# CarteAction_PontLevis2026.net
KiCad netlist of a schematic drawn in Altium Designer
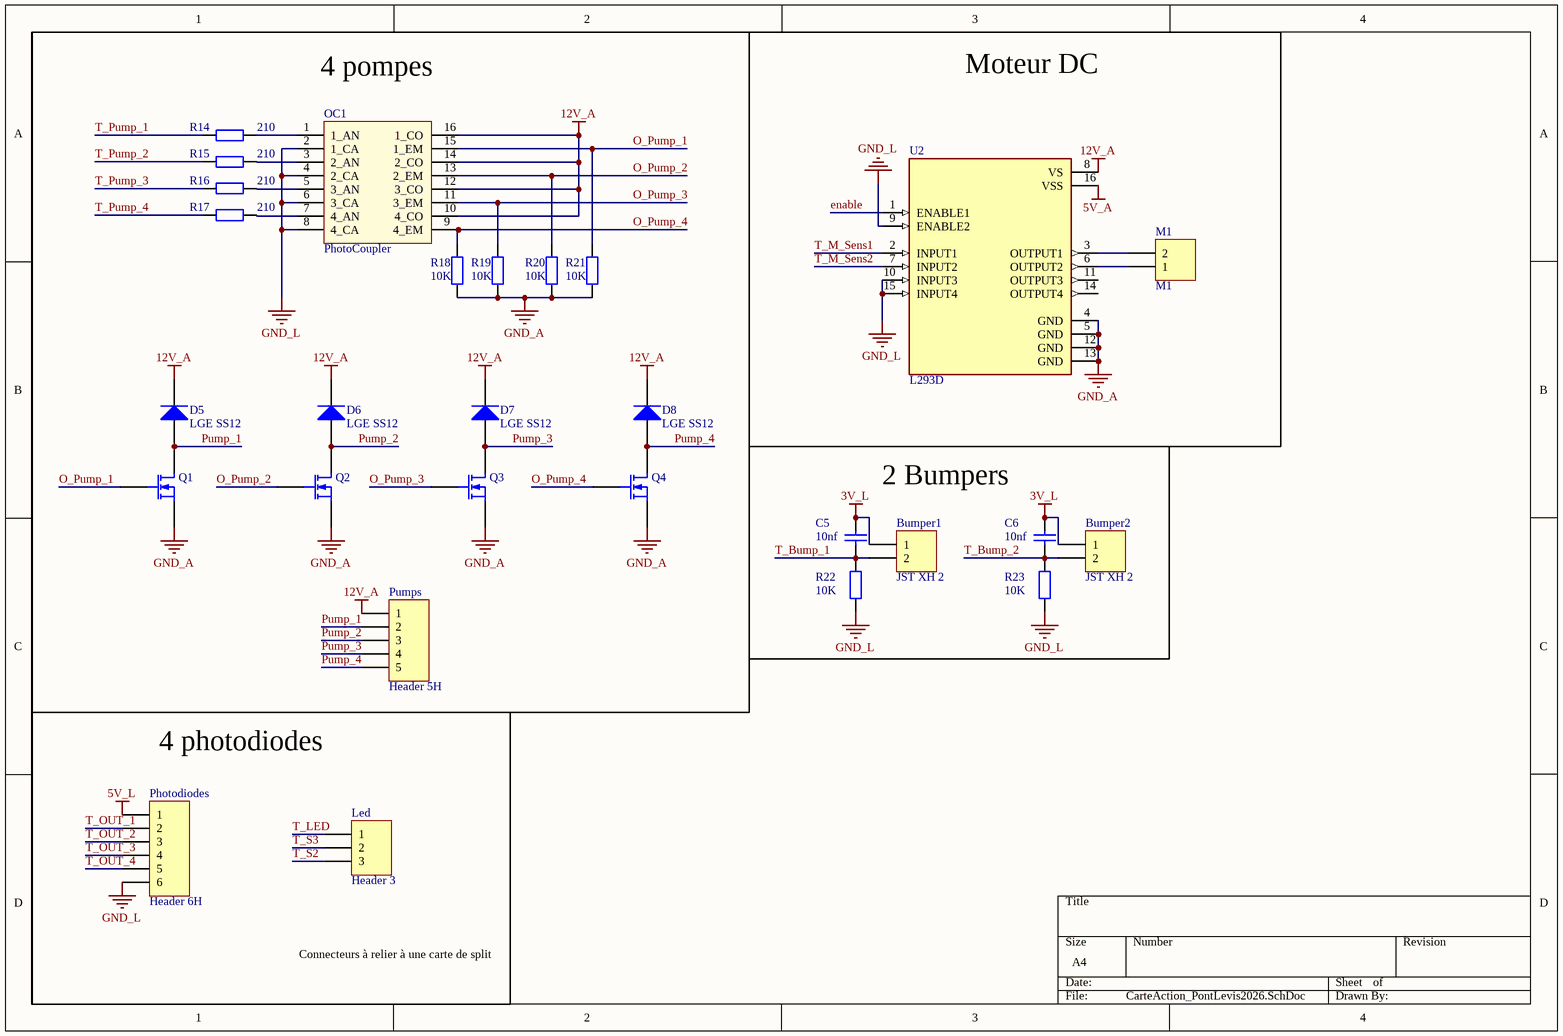
[diagram p0: CarteAction_PontLevis2026.SchDoc]

(export (version "E")
  (design (tool "Eeschema 10.0.6"))
  (components
    (comp (ref "Bumper1")
      (value "JST XH 2")
      (footprint "S2B-XH-A")
      (description "Header, 2-Pin")
      (fields (field (name "PUBLISHER") "Altium Limited"))
      (libsource (lib "Miscellaneous Connectors") (part "Header 2"))
    )
    (comp (ref "Bumper2")
      (value "JST XH 2")
      (footprint "S2B-XH-A")
      (description "Header, 2-Pin")
      (fields (field (name "PUBLISHER") "Altium Limited"))
      (libsource (lib "Miscellaneous Connectors") (part "Header 2"))
    )
    (comp (ref "C5")
      (value "10nf")
      (footprint "Capacitor 1206")
      (description "Capacitor")
      (fields (field (name "Comment") "Cap") (field (name "PUBLISHER") "Altium Limited"))
      (libsource (lib "Miscellaneous Devices") (part "Cap"))
    )
    (comp (ref "C6")
      (value "10nf")
      (footprint "Capacitor 1206")
      (description "Capacitor")
      (fields (field (name "Comment") "Cap") (field (name "PUBLISHER") "Altium Limited"))
      (libsource (lib "Miscellaneous Devices") (part "Cap"))
    )
    (comp (ref "D5")
      (value "LGE SS12")
      (footprint "SMB")
      (description "Default Diode")
      (fields (field (name "PUBLISHER") "Altium Limited"))
      (libsource (lib "Miscellaneous Devices") (part "Diode"))
    )
    (comp (ref "D6")
      (value "LGE SS12")
      (footprint "SMB")
      (description "Default Diode")
      (fields (field (name "PUBLISHER") "Altium Limited"))
      (libsource (lib "Miscellaneous Devices") (part "Diode"))
    )
    (comp (ref "D7")
      (value "LGE SS12")
      (footprint "SMB")
      (description "Default Diode")
      (fields (field (name "PUBLISHER") "Altium Limited"))
      (libsource (lib "Miscellaneous Devices") (part "Diode"))
    )
    (comp (ref "D8")
      (value "LGE SS12")
      (footprint "SMB")
      (description "Default Diode")
      (fields (field (name "PUBLISHER") "Altium Limited"))
      (libsource (lib "Miscellaneous Devices") (part "Diode"))
    )
    (comp (ref "Led")
      (value "Header 3")
      (footprint "S3B-XH-A")
      (description "Header, 3-Pin")
      (fields (field (name "PUBLISHER") "Altium Limited"))
      (libsource (lib "Miscellaneous Connectors") (part "Header 3"))
    )
    (comp (ref "M1")
      (value "M1")
      (footprint "S2B-XH-A")
      (description "Header, 2-Pin, Right Angle")
      (fields (field (name "PUBLISHER") "Altium Limited"))
      (libsource (lib "Miscellaneous Connectors") (part "Header 2H"))
    )
    (comp (ref "OC1")
      (value "PhotoCoupler")
      (footprint "16 pins SOIC, TI")
      (description "Integrated Circuit")
      (fields
        (field (name "MANUFACTURER_PART_NUMBER") "LTV-247")
        (field (name "MOUSER PART NUMBER") "859-LTV-247")
      )
      (libsource (lib "SamacSys") (part "LTV-247"))
    )
    (comp (ref "Photodiodes")
      (value "Header 6H")
      (footprint "S6B-XH-A")
      (description "Header, 6-Pin, Right Angle")
      (fields (field (name "PUBLISHER") "Altium Limited"))
      (libsource (lib "Miscellaneous Connectors") (part "Header 6H"))
    )
    (comp (ref "Pumps")
      (value "Header 5H")
      (footprint "S5B-XH-A")
      (description "Header, 5-Pin, Right Angle")
      (fields (field (name "PUBLISHER") "Altium Limited"))
      (libsource (lib "Miscellaneous Connectors") (part "Header 5H"))
    )
    (comp (ref "Q1")
      (value "MOSFET-N")
      (footprint "SOT23_M")
      (description "N-Channel MOSFET")
      (fields (field (name "PUBLISHER") "Altium Limited"))
      (libsource (lib "Miscellaneous Devices") (part "MOSFET-N"))
    )
    (comp (ref "Q2")
      (value "MOSFET-N")
      (footprint "SOT23_M")
      (description "N-Channel MOSFET")
      (fields (field (name "PUBLISHER") "Altium Limited"))
      (libsource (lib "Miscellaneous Devices") (part "MOSFET-N"))
    )
    (comp (ref "Q3")
      (value "MOSFET-N")
      (footprint "SOT23_M")
      (description "N-Channel MOSFET")
      (fields (field (name "PUBLISHER") "Altium Limited"))
      (libsource (lib "Miscellaneous Devices") (part "MOSFET-N"))
    )
    (comp (ref "Q4")
      (value "MOSFET-N")
      (footprint "SOT23_M")
      (description "N-Channel MOSFET")
      (fields (field (name "PUBLISHER") "Altium Limited"))
      (libsource (lib "Miscellaneous Devices") (part "MOSFET-N"))
    )
    (comp (ref "R14")
      (value "210")
      (footprint "Resistor 1206")
      (description "Resistor")
      (fields (field (name "Comment") "Res2") (field (name "PUBLISHER") "Altium Limited"))
      (libsource (lib "") (part "Res2_1"))
    )
    (comp (ref "R15")
      (value "210")
      (footprint "Resistor 1206")
      (description "Resistor")
      (fields (field (name "Comment") "Res2") (field (name "PUBLISHER") "Altium Limited"))
      (libsource (lib "") (part "Res2_1"))
    )
    (comp (ref "R16")
      (value "210")
      (footprint "Resistor 1206")
      (description "Resistor")
      (fields (field (name "Comment") "Res2") (field (name "PUBLISHER") "Altium Limited"))
      (libsource (lib "") (part "Res2_1"))
    )
    (comp (ref "R17")
      (value "210")
      (footprint "Resistor 1206")
      (description "Resistor")
      (fields (field (name "Comment") "Res2") (field (name "PUBLISHER") "Altium Limited"))
      (libsource (lib "") (part "Res2_1"))
    )
    (comp (ref "R18")
      (value "10K")
      (footprint "Resistor 1206")
      (description "Resistor")
      (fields (field (name "Comment") "Res2") (field (name "PUBLISHER") "Altium Limited"))
      (libsource (lib "Miscellaneous Devices") (part "Res2"))
    )
    (comp (ref "R19")
      (value "10K")
      (footprint "Resistor 1206")
      (description "Resistor")
      (fields (field (name "Comment") "Res2") (field (name "PUBLISHER") "Altium Limited"))
      (libsource (lib "Miscellaneous Devices") (part "Res2"))
    )
    (comp (ref "R20")
      (value "10K")
      (footprint "Resistor 1206")
      (description "Resistor")
      (fields (field (name "Comment") "Res2") (field (name "PUBLISHER") "Altium Limited"))
      (libsource (lib "Miscellaneous Devices") (part "Res2"))
    )
    (comp (ref "R21")
      (value "10K")
      (footprint "Resistor 1206")
      (description "Resistor")
      (fields (field (name "Comment") "Res2") (field (name "PUBLISHER") "Altium Limited"))
      (libsource (lib "Miscellaneous Devices") (part "Res2"))
    )
    (comp (ref "R22")
      (value "10K")
      (footprint "Resistor 1206")
      (description "Resistor")
      (fields (field (name "Comment") "Res2") (field (name "PUBLISHER") "Altium Limited"))
      (libsource (lib "") (part "Res2_2"))
    )
    (comp (ref "R23")
      (value "10K")
      (footprint "Resistor 1206")
      (description "Resistor")
      (fields (field (name "Comment") "Res2") (field (name "PUBLISHER") "Altium Limited"))
      (libsource (lib "") (part "Res2_2"))
    )
    (comp (ref "U2")
      (value "L293D")
      (footprint "DIP880W50P254L2000H510Q16")
      (description "Bipolar Motor Driver - Parallel 16-PowerDIP")
      (fields (field (name "MF") "STMicroelectronics"))
      (libsource (lib "L293D") (part "L293D"))
    )
  )
  (nets
    (net (code "1") (name "/O_Pump_1") (class "Default")
      (node (ref "OC1") (pin "15") (pinfunction "1_EM_15") (pintype "passive"))
      (node (ref "Q1") (pin "2") (pinfunction "G_2") (pintype "passive"))
      (node (ref "R21") (pin "2") (pinfunction "2_2") (pintype "passive"))
    )
    (net (code "2") (name "/O_Pump_2") (class "Default")
      (node (ref "OC1") (pin "13") (pinfunction "2_EM_13") (pintype "passive"))
      (node (ref "Q2") (pin "2") (pinfunction "G_2") (pintype "passive"))
      (node (ref "R20") (pin "2") (pinfunction "2_2") (pintype "passive"))
    )
    (net (code "3") (name "/O_Pump_3") (class "Default")
      (node (ref "OC1") (pin "11") (pinfunction "3_EM_11") (pintype "passive"))
      (node (ref "Q3") (pin "2") (pinfunction "G_2") (pintype "passive"))
      (node (ref "R19") (pin "2") (pinfunction "2_2") (pintype "passive"))
    )
    (net (code "4") (name "/O_Pump_4") (class "Default")
      (node (ref "OC1") (pin "9") (pinfunction "4_EM_9") (pintype "passive"))
      (node (ref "Q4") (pin "2") (pinfunction "G_2") (pintype "passive"))
      (node (ref "R18") (pin "2") (pinfunction "2_2") (pintype "passive"))
    )
    (net (code "5") (name "/Pump_1") (class "Default")
      (node (ref "D5") (pin "1") (pinfunction "A_1") (pintype "passive"))
      (node (ref "Pumps") (pin "2") (pinfunction "2_2") (pintype "passive"))
      (node (ref "Q1") (pin "1") (pinfunction "D_1") (pintype "passive"))
    )
    (net (code "6") (name "/Pump_2") (class "Default")
      (node (ref "D6") (pin "1") (pinfunction "A_1") (pintype "passive"))
      (node (ref "Pumps") (pin "3") (pinfunction "3_3") (pintype "passive"))
      (node (ref "Q2") (pin "1") (pinfunction "D_1") (pintype "passive"))
    )
    (net (code "7") (name "/Pump_3") (class "Default")
      (node (ref "D7") (pin "1") (pinfunction "A_1") (pintype "passive"))
      (node (ref "Pumps") (pin "4") (pinfunction "4_4") (pintype "passive"))
      (node (ref "Q3") (pin "1") (pinfunction "D_1") (pintype "passive"))
    )
    (net (code "8") (name "/Pump_4") (class "Default")
      (node (ref "D8") (pin "1") (pinfunction "A_1") (pintype "passive"))
      (node (ref "Pumps") (pin "5") (pinfunction "5_5") (pintype "passive"))
      (node (ref "Q4") (pin "1") (pinfunction "D_1") (pintype "passive"))
    )
    (net (code "9") (name "/T_Bump_1") (class "Default")
      (node (ref "Bumper1") (pin "2") (pinfunction "2_2") (pintype "passive"))
      (node (ref "C5") (pin "1") (pinfunction "1_1") (pintype "passive"))
      (node (ref "R22") (pin "1") (pinfunction "1_1") (pintype "passive"))
    )
    (net (code "10") (name "/T_Bump_2") (class "Default")
      (node (ref "Bumper2") (pin "2") (pinfunction "2_2") (pintype "passive"))
      (node (ref "C6") (pin "1") (pinfunction "1_1") (pintype "passive"))
      (node (ref "R23") (pin "1") (pinfunction "1_1") (pintype "passive"))
    )
    (net (code "11") (name "/T_LED") (class "Default")
      (node (ref "Led") (pin "1") (pinfunction "1_1") (pintype "passive"))
    )
    (net (code "12") (name "/T_M_Sens1") (class "Default")
      (node (ref "U2") (pin "2") (pinfunction "INPUT1_2") (pintype "input"))
    )
    (net (code "13") (name "/T_M_Sens2") (class "Default")
      (node (ref "U2") (pin "7") (pinfunction "INPUT2_7") (pintype "input"))
    )
    (net (code "14") (name "/T_OUT_1") (class "Default")
      (node (ref "Photodiodes") (pin "2") (pinfunction "2_2") (pintype "passive"))
    )
    (net (code "15") (name "/T_OUT_2") (class "Default")
      (node (ref "Photodiodes") (pin "3") (pinfunction "3_3") (pintype "passive"))
    )
    (net (code "16") (name "/T_OUT_3") (class "Default")
      (node (ref "Photodiodes") (pin "4") (pinfunction "4_4") (pintype "passive"))
    )
    (net (code "17") (name "/T_OUT_4") (class "Default")
      (node (ref "Photodiodes") (pin "5") (pinfunction "5_5") (pintype "passive"))
    )
    (net (code "18") (name "/T_Pump_1") (class "Default")
      (node (ref "R14") (pin "2") (pinfunction "2_2") (pintype "passive"))
    )
    (net (code "19") (name "/T_Pump_2") (class "Default")
      (node (ref "R15") (pin "2") (pinfunction "2_2") (pintype "passive"))
    )
    (net (code "20") (name "/T_Pump_3") (class "Default")
      (node (ref "R16") (pin "2") (pinfunction "2_2") (pintype "passive"))
    )
    (net (code "21") (name "/T_Pump_4") (class "Default")
      (node (ref "R17") (pin "2") (pinfunction "2_2") (pintype "passive"))
    )
    (net (code "22") (name "/T_S2") (class "Default")
      (node (ref "Led") (pin "3") (pinfunction "3_3") (pintype "passive"))
    )
    (net (code "23") (name "/T_S3") (class "Default")
      (node (ref "Led") (pin "2") (pinfunction "2_2") (pintype "passive"))
    )
    (net (code "24") (name "/enable") (class "Default")
      (node (ref "U2") (pin "1") (pinfunction "ENABLE1_1") (pintype "input"))
    )
    (net (code "25") (name "3V_L") (class "Default")
      (node (ref "Bumper1") (pin "1") (pinfunction "1_1") (pintype "passive"))
      (node (ref "Bumper2") (pin "1") (pinfunction "1_1") (pintype "passive"))
      (node (ref "C5") (pin "2") (pinfunction "2_2") (pintype "passive"))
      (node (ref "C6") (pin "2") (pinfunction "2_2") (pintype "passive"))
    )
    (net (code "26") (name "5V_A") (class "Default")
      (node (ref "U2") (pin "16") (pinfunction "VSS_16") (pintype "power_in"))
    )
    (net (code "27") (name "5V_L") (class "Default")
      (node (ref "Photodiodes") (pin "1") (pinfunction "1_1") (pintype "passive"))
    )
    (net (code "28") (name "12V_A") (class "Default")
      (node (ref "D5") (pin "2") (pinfunction "K_2") (pintype "passive"))
      (node (ref "D6") (pin "2") (pinfunction "K_2") (pintype "passive"))
      (node (ref "D7") (pin "2") (pinfunction "K_2") (pintype "passive"))
      (node (ref "D8") (pin "2") (pinfunction "K_2") (pintype "passive"))
      (node (ref "OC1") (pin "10") (pinfunction "4_CO_10") (pintype "passive"))
      (node (ref "OC1") (pin "12") (pinfunction "3_CO_12") (pintype "passive"))
      (node (ref "OC1") (pin "14") (pinfunction "2_CO_14") (pintype "passive"))
      (node (ref "OC1") (pin "16") (pinfunction "1_CO_16") (pintype "passive"))
      (node (ref "Pumps") (pin "1") (pinfunction "1_1") (pintype "passive"))
      (node (ref "U2") (pin "8") (pinfunction "VS_8") (pintype "power_in"))
    )
    (net (code "29") (name "GND_A") (class "Default")
      (node (ref "Q1") (pin "3") (pinfunction "S_3") (pintype "passive"))
      (node (ref "Q2") (pin "3") (pinfunction "S_3") (pintype "passive"))
      (node (ref "Q3") (pin "3") (pinfunction "S_3") (pintype "passive"))
      (node (ref "Q4") (pin "3") (pinfunction "S_3") (pintype "passive"))
      (node (ref "R18") (pin "1") (pinfunction "1_1") (pintype "passive"))
      (node (ref "R19") (pin "1") (pinfunction "1_1") (pintype "passive"))
      (node (ref "R20") (pin "1") (pinfunction "1_1") (pintype "passive"))
      (node (ref "R21") (pin "1") (pinfunction "1_1") (pintype "passive"))
      (node (ref "U2") (pin "12") (pinfunction "GND_12") (pintype "power_in"))
      (node (ref "U2") (pin "13") (pinfunction "GND_13") (pintype "power_in"))
      (node (ref "U2") (pin "4") (pinfunction "GND_4") (pintype "power_in"))
      (node (ref "U2") (pin "5") (pinfunction "GND_5") (pintype "power_in"))
    )
    (net (code "30") (name "GND_L") (class "Default")
      (node (ref "OC1") (pin "2") (pinfunction "1_CA_2") (pintype "passive"))
      (node (ref "OC1") (pin "4") (pinfunction "2_CA_4") (pintype "passive"))
      (node (ref "OC1") (pin "6") (pinfunction "3_CA_6") (pintype "passive"))
      (node (ref "OC1") (pin "8") (pinfunction "4_CA_8") (pintype "passive"))
      (node (ref "Photodiodes") (pin "6") (pinfunction "6_6") (pintype "passive"))
      (node (ref "R22") (pin "2") (pinfunction "2_2") (pintype "passive"))
      (node (ref "R23") (pin "2") (pinfunction "2_2") (pintype "passive"))
      (node (ref "U2") (pin "10") (pinfunction "INPUT3_10") (pintype "input"))
      (node (ref "U2") (pin "15") (pinfunction "INPUT4_15") (pintype "input"))
      (node (ref "U2") (pin "9") (pinfunction "ENABLE2_9") (pintype "input"))
    )
    (net (code "31") (name "Net-(OC1-1_AN)") (class "Default")
      (node (ref "OC1") (pin "1") (pinfunction "1_AN_1") (pintype "passive"))
      (node (ref "R14") (pin "1") (pinfunction "1_1") (pintype "passive"))
    )
    (net (code "32") (name "Net-(OC1-2_AN)") (class "Default")
      (node (ref "OC1") (pin "3") (pinfunction "2_AN_3") (pintype "passive"))
      (node (ref "R15") (pin "1") (pinfunction "1_1") (pintype "passive"))
    )
    (net (code "33") (name "Net-(OC1-3_AN)") (class "Default")
      (node (ref "OC1") (pin "5") (pinfunction "3_AN_5") (pintype "passive"))
      (node (ref "R16") (pin "1") (pinfunction "1_1") (pintype "passive"))
    )
    (net (code "34") (name "Net-(OC1-4_AN)") (class "Default")
      (node (ref "OC1") (pin "7") (pinfunction "4_AN_7") (pintype "passive"))
      (node (ref "R17") (pin "1") (pinfunction "1_1") (pintype "passive"))
    )
    (net (code "35") (name "Net-(U2-OUTPUT1)") (class "Default")
      (node (ref "M1") (pin "2") (pinfunction "2_2") (pintype "passive"))
      (node (ref "U2") (pin "3") (pinfunction "OUTPUT1_3") (pintype "output"))
    )
    (net (code "36") (name "Net-(U2-OUTPUT2)") (class "Default")
      (node (ref "M1") (pin "1") (pinfunction "1_1") (pintype "passive"))
      (node (ref "U2") (pin "6") (pinfunction "OUTPUT2_6") (pintype "output"))
    )
    (net (code "37") (name "unconnected-(U2-OUTPUT3-Pad11)") (class "Default")
      (node (ref "U2") (pin "11") (pinfunction "OUTPUT3_11") (pintype "output"))
    )
    (net (code "38") (name "unconnected-(U2-OUTPUT4-Pad14)") (class "Default")
      (node (ref "U2") (pin "14") (pinfunction "OUTPUT4_14") (pintype "output"))
    )
  )
)
